# Pinscape_Pico-KL25Z_Adapter.net
KiCad netlist of a schematic drawn in EAGLE
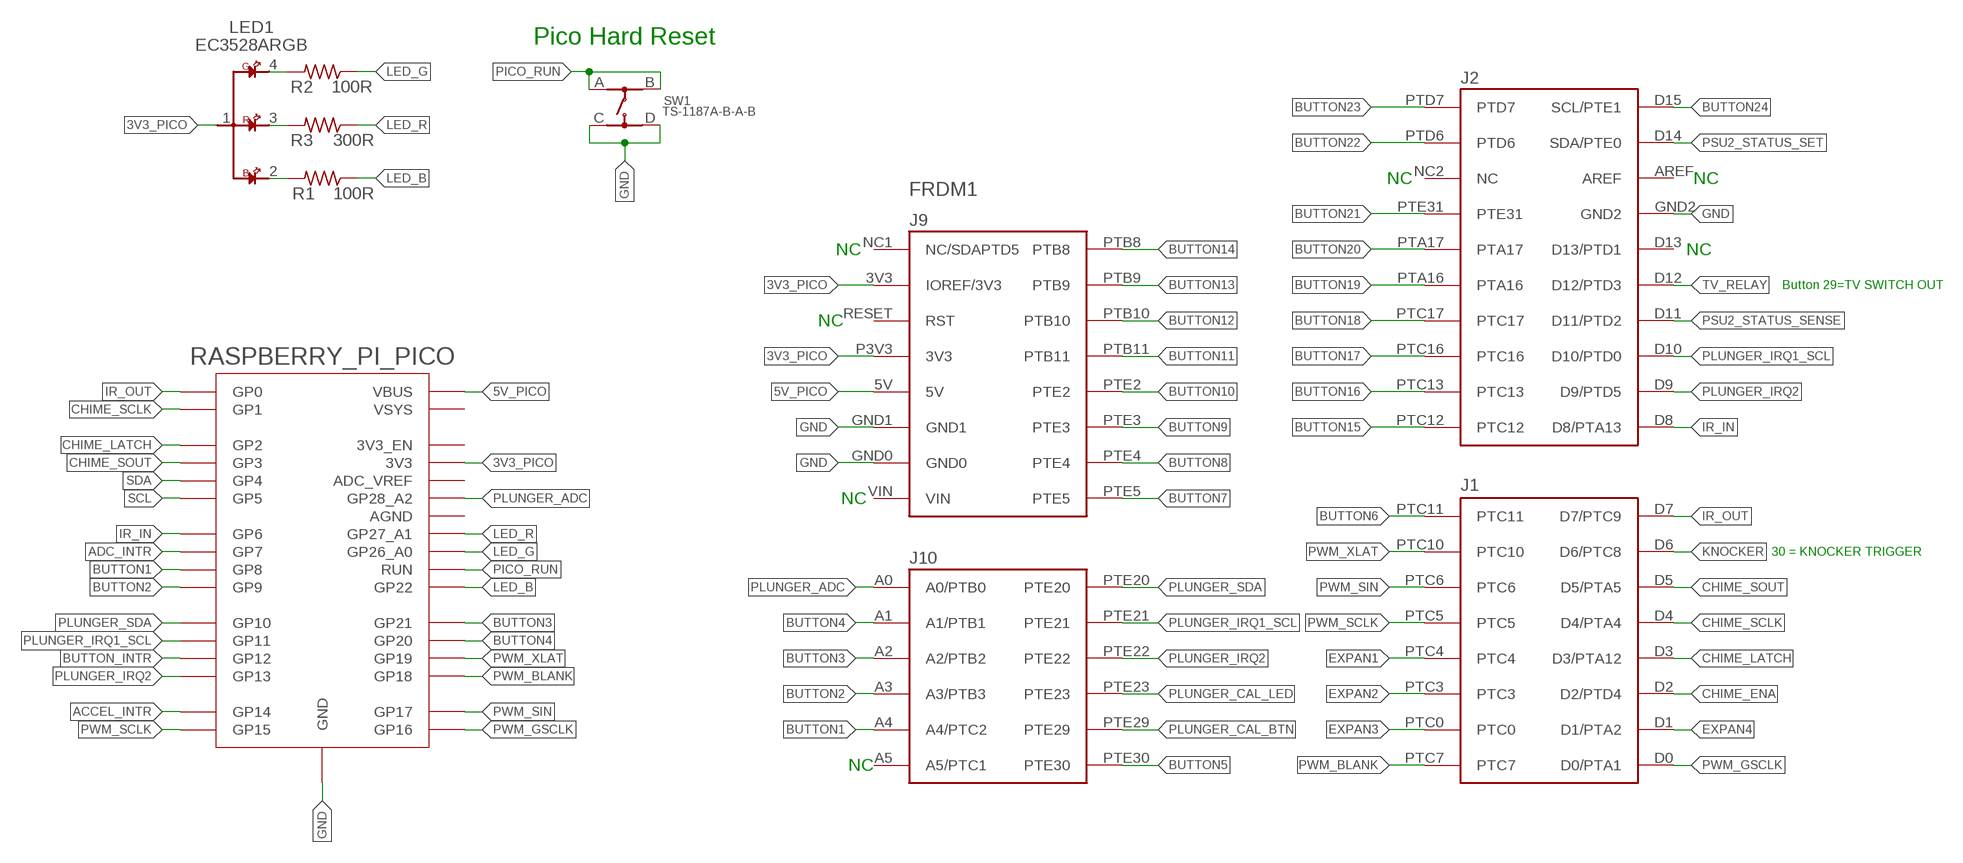
[diagram p0: schematic, sheet 1]
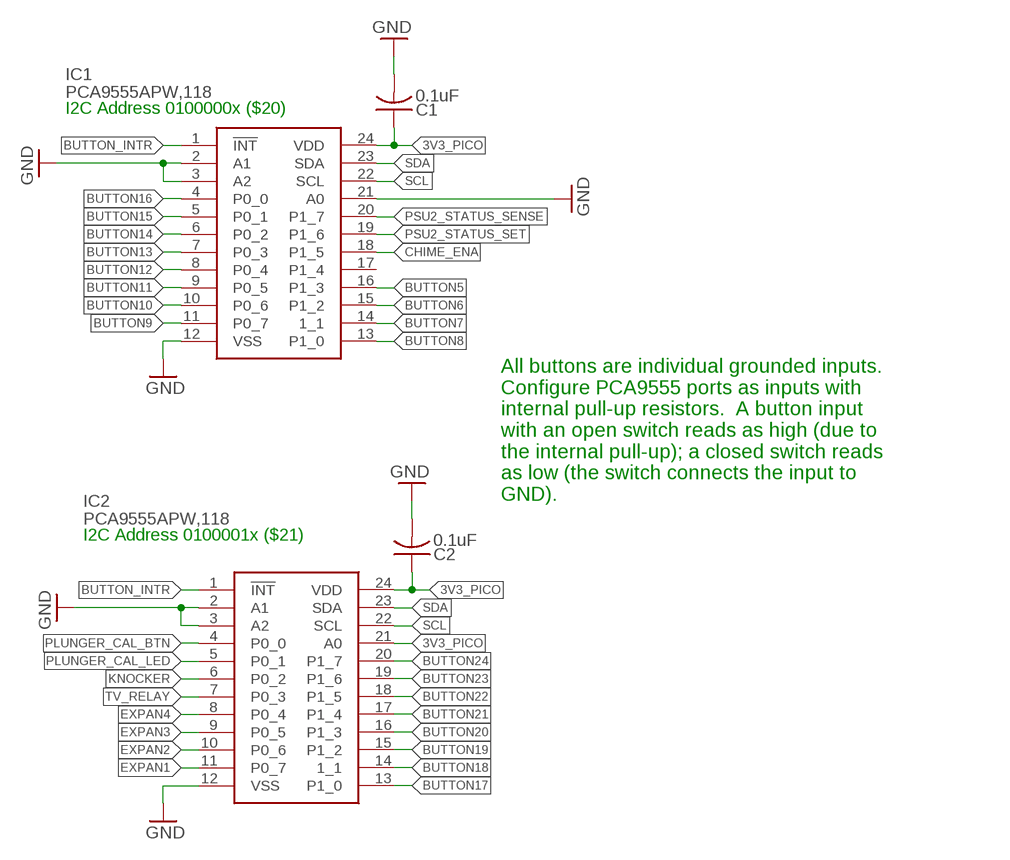
[diagram p1: schematic, sheet 2]
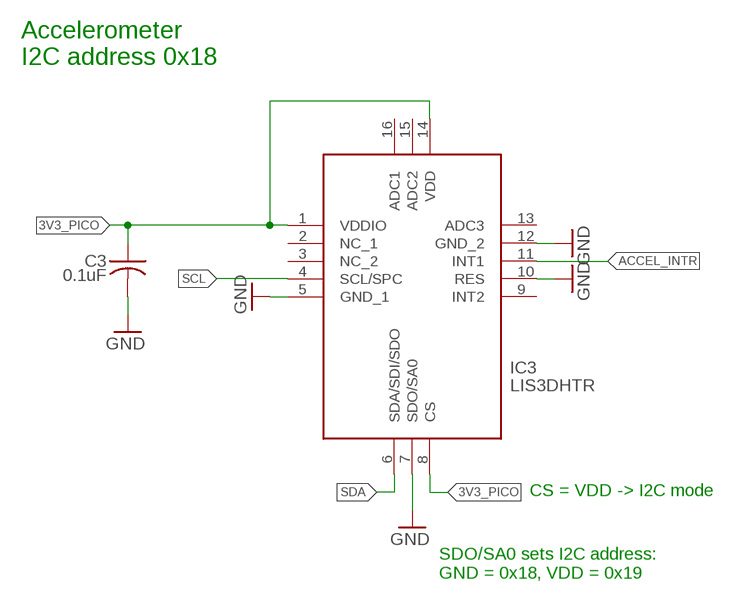
[diagram p2: schematic, sheet 3]
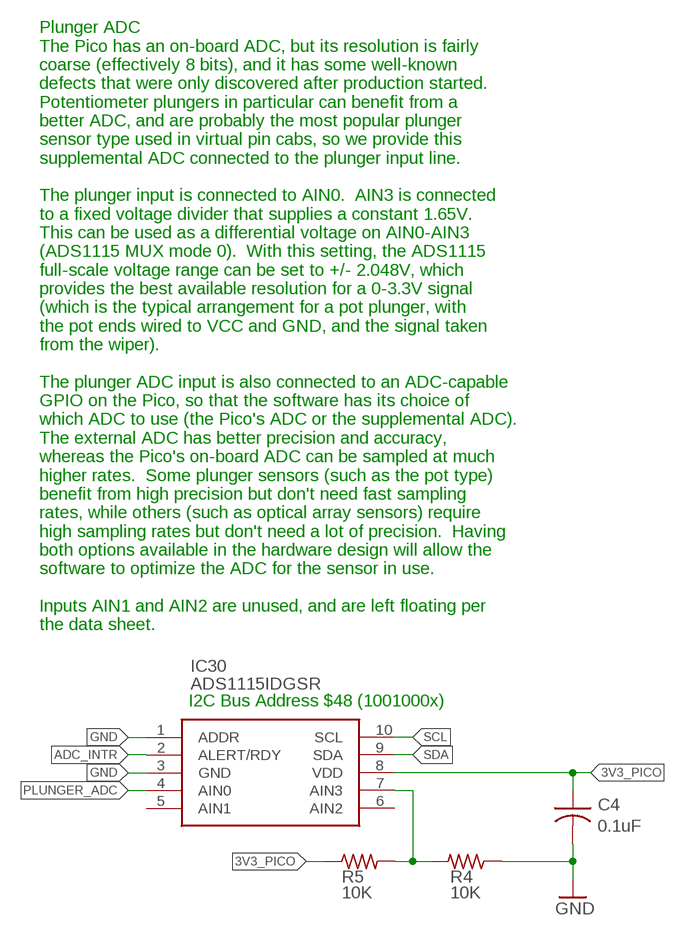
[diagram p3: schematic, sheet 4]

(export (version "E")
  (design (tool "Eeschema 10.0.6"))
  (components
    (comp (ref "FRDM1")
      (value "KL25Z")
      (footprint "eagle-import:FRDM_KL25Z_NORMAL")
      (libsource (lib "eagle-import") (part "FRDM-KL25ZNORMAL"))
    )
    (comp (ref "LED1")
      (value "EC3528ARGB")
      (footprint "eagle-import:EC3528ARGB")
      (libsource (lib "eagle-import") (part "EC3528ARGB"))
    )
    (comp (ref "R1")
      (value "100R")
      (footprint "eagle-import:R1206")
      (libsource (lib "eagle-import") (part "R-US_R1206"))
    )
    (comp (ref "R2")
      (value "100R")
      (footprint "eagle-import:R1206")
      (libsource (lib "eagle-import") (part "R-US_R1206"))
    )
    (comp (ref "R3")
      (value "300R")
      (footprint "eagle-import:R1206")
      (libsource (lib "eagle-import") (part "R-US_R1206"))
    )
    (comp (ref "RASPBERRY_PI_PICO")
      (value "RPI_PICO_NO_DEBUG")
      (footprint "eagle-import:RPI_PICO_TH_NO_DEBUG")
      (libsource (lib "eagle-import") (part "RPI_PICO_NO_DEBUG"))
    )
    (comp (ref "SW1")
      (value "TS-1187A-B-A-B")
      (footprint "eagle-import:TS-1187A-B-A-B")
      (libsource (lib "eagle-import") (part "TS-1187A-B-A-B"))
    )
    (comp (ref "C1")
      (value "0.1uF")
      (footprint "eagle-import:C1206")
      (libsource (lib "eagle-import") (part "C-USC1206"))
    )
    (comp (ref "C2")
      (value "0.1uF")
      (footprint "eagle-import:C1206")
      (libsource (lib "eagle-import") (part "C-USC1206"))
    )
    (comp (ref "IC1")
      (value "PCA9555APW,118")
      (footprint "eagle-import:SOP65P640X110-24N")
      (fields (field (name "MOUSER_PART_NUMBER") "771-PCA9555APW118"))
      (libsource (lib "eagle-import") (part "PCA9555APW,118"))
    )
    (comp (ref "IC2")
      (value "PCA9555APW,118")
      (footprint "eagle-import:SOP65P640X110-24N")
      (fields (field (name "MOUSER_PART_NUMBER") "771-PCA9555APW118"))
      (libsource (lib "eagle-import") (part "PCA9555APW,118"))
    )
    (comp (ref "C4")
      (value "0.1uF")
      (footprint "eagle-import:C1206")
      (libsource (lib "eagle-import") (part "C-USC1206"))
    )
    (comp (ref "IC30")
      (value "ADS1115IDGSR")
      (footprint "eagle-import:SOP50P490X110-10N")
      (fields (field (name "MOUSER_PART_NUMBER") "595-ADS1115IDGSR"))
      (libsource (lib "eagle-import") (part "ADS1115IDGSR"))
    )
    (comp (ref "R4")
      (value "10K")
      (footprint "eagle-import:R1206")
      (libsource (lib "eagle-import") (part "R-US_R1206"))
    )
    (comp (ref "R5")
      (value "10K")
      (footprint "eagle-import:R1206")
      (libsource (lib "eagle-import") (part "R-US_R1206"))
    )
    (comp (ref "C3")
      (value "0.1uF")
      (footprint "eagle-import:C1206")
      (libsource (lib "eagle-import") (part "C-USC1206"))
    )
    (comp (ref "IC3")
      (value "LIS3DHTR")
      (footprint "eagle-import:LIS3DHTR")
      (fields (field (name "MOUSER_PART_NUMBER") "511-LIS3DHTR"))
      (libsource (lib "eagle-import") (part "LIS3DHTR"))
    )
  )
  (nets
    (net (code "1") (name "3V3_PICO") (class "Default")
      (node (ref "C1") (pin "1") (pinfunction "1_1") (pintype "passive"))
      (node (ref "C2") (pin "1") (pinfunction "1_1") (pintype "passive"))
      (node (ref "C3") (pin "1") (pinfunction "1_1") (pintype "passive"))
      (node (ref "C4") (pin "1") (pinfunction "1_1") (pintype "passive"))
      (node (ref "FRDM1") (pin "3V3") (pinfunction "IOREF/3V3_3V3") (pintype "bidirectional"))
      (node (ref "FRDM1") (pin "P3V3") (pinfunction "3V3_P3V3") (pintype "bidirectional"))
      (node (ref "IC1") (pin "24") (pinfunction "VDD_24") (pintype "bidirectional"))
      (node (ref "IC2") (pin "21") (pinfunction "A0_21") (pintype "bidirectional"))
      (node (ref "IC2") (pin "24") (pinfunction "VDD_24") (pintype "bidirectional"))
      (node (ref "IC3") (pin "1") (pinfunction "VDDIO_1") (pintype "power_in"))
      (node (ref "IC3") (pin "14") (pinfunction "VDD_14") (pintype "power_in"))
      (node (ref "IC3") (pin "8") (pinfunction "CS_8") (pintype "input"))
      (node (ref "IC30") (pin "8") (pinfunction "VDD_8") (pintype "bidirectional"))
      (node (ref "LED1") (pin "1") (pinfunction "1_1") (pintype "bidirectional"))
      (node (ref "R5") (pin "1") (pinfunction "1_1") (pintype "passive"))
      (node (ref "RASPBERRY_PI_PICO") (pin "3V3") (pinfunction "3V3_3V3") (pintype "bidirectional"))
    )
    (net (code "2") (name "5V_PICO") (class "Default")
      (node (ref "FRDM1") (pin "5V") (pinfunction "5V_5V") (pintype "bidirectional"))
      (node (ref "RASPBERRY_PI_PICO") (pin "VBUS") (pinfunction "VBUS_VBUS") (pintype "bidirectional"))
    )
    (net (code "3") (name "ACCEL_INTR") (class "Default")
      (node (ref "IC3") (pin "11") (pinfunction "INT1_11") (pintype "input"))
      (node (ref "RASPBERRY_PI_PICO") (pin "GP14") (pinfunction "GP14_GP14") (pintype "bidirectional"))
    )
    (net (code "4") (name "ADC_INTR") (class "Default")
      (node (ref "IC30") (pin "2") (pinfunction "ALERT/RDY_2") (pintype "bidirectional"))
      (node (ref "RASPBERRY_PI_PICO") (pin "GP7") (pinfunction "GP7_GP7") (pintype "bidirectional"))
    )
    (net (code "5") (name "BUTTON1") (class "Default")
      (node (ref "FRDM1") (pin "A4") (pinfunction "A4/PTC2_A4") (pintype "bidirectional"))
      (node (ref "RASPBERRY_PI_PICO") (pin "GP8") (pinfunction "GP8_GP8") (pintype "bidirectional"))
    )
    (net (code "6") (name "BUTTON2") (class "Default")
      (node (ref "FRDM1") (pin "A3") (pinfunction "A3/PTB3_A3") (pintype "bidirectional"))
      (node (ref "RASPBERRY_PI_PICO") (pin "GP9") (pinfunction "GP9_GP9") (pintype "bidirectional"))
    )
    (net (code "7") (name "BUTTON3") (class "Default")
      (node (ref "FRDM1") (pin "A2") (pinfunction "A2/PTB2_A2") (pintype "bidirectional"))
      (node (ref "RASPBERRY_PI_PICO") (pin "GP21") (pinfunction "GP21_GP21") (pintype "bidirectional"))
    )
    (net (code "8") (name "BUTTON4") (class "Default")
      (node (ref "FRDM1") (pin "A1") (pinfunction "A1/PTB1_A1") (pintype "bidirectional"))
      (node (ref "RASPBERRY_PI_PICO") (pin "GP20") (pinfunction "GP20_GP20") (pintype "bidirectional"))
    )
    (net (code "9") (name "BUTTON5") (class "Default")
      (node (ref "FRDM1") (pin "PTE30") (pinfunction "PTE30_PTE30") (pintype "bidirectional"))
      (node (ref "IC1") (pin "16") (pinfunction "P1_3_16") (pintype "bidirectional"))
    )
    (net (code "10") (name "BUTTON6") (class "Default")
      (node (ref "FRDM1") (pin "PTC11") (pinfunction "PTC11_PTC11") (pintype "bidirectional"))
      (node (ref "IC1") (pin "15") (pinfunction "P1_2_15") (pintype "bidirectional"))
    )
    (net (code "11") (name "BUTTON7") (class "Default")
      (node (ref "FRDM1") (pin "PTE5") (pinfunction "PTE5_PTE5") (pintype "bidirectional"))
      (node (ref "IC1") (pin "14") (pinfunction "1_1_14") (pintype "bidirectional"))
    )
    (net (code "12") (name "BUTTON8") (class "Default")
      (node (ref "FRDM1") (pin "PTE4") (pinfunction "PTE4_PTE4") (pintype "bidirectional"))
      (node (ref "IC1") (pin "13") (pinfunction "P1_0_13") (pintype "bidirectional"))
    )
    (net (code "13") (name "BUTTON9") (class "Default")
      (node (ref "FRDM1") (pin "PTE3") (pinfunction "PTE3_PTE3") (pintype "bidirectional"))
      (node (ref "IC1") (pin "11") (pinfunction "P0_7_11") (pintype "bidirectional"))
    )
    (net (code "14") (name "BUTTON10") (class "Default")
      (node (ref "FRDM1") (pin "PTE2") (pinfunction "PTE2_PTE2") (pintype "bidirectional"))
      (node (ref "IC1") (pin "10") (pinfunction "P0_6_10") (pintype "bidirectional"))
    )
    (net (code "15") (name "BUTTON11") (class "Default")
      (node (ref "FRDM1") (pin "PTB11") (pinfunction "PTB11_PTB11") (pintype "bidirectional"))
      (node (ref "IC1") (pin "9") (pinfunction "P0_5_9") (pintype "bidirectional"))
    )
    (net (code "16") (name "BUTTON12") (class "Default")
      (node (ref "FRDM1") (pin "PTB10") (pinfunction "PTB10_PTB10") (pintype "bidirectional"))
      (node (ref "IC1") (pin "8") (pinfunction "P0_4_8") (pintype "bidirectional"))
    )
    (net (code "17") (name "BUTTON13") (class "Default")
      (node (ref "FRDM1") (pin "PTB9") (pinfunction "PTB9_PTB9") (pintype "bidirectional"))
      (node (ref "IC1") (pin "7") (pinfunction "P0_3_7") (pintype "bidirectional"))
    )
    (net (code "18") (name "BUTTON14") (class "Default")
      (node (ref "FRDM1") (pin "PTB8") (pinfunction "PTB8_PTB8") (pintype "bidirectional"))
      (node (ref "IC1") (pin "6") (pinfunction "P0_2_6") (pintype "bidirectional"))
    )
    (net (code "19") (name "BUTTON15") (class "Default")
      (node (ref "FRDM1") (pin "PTC12") (pinfunction "PTC12_PTC12") (pintype "bidirectional"))
      (node (ref "IC1") (pin "5") (pinfunction "P0_1_5") (pintype "bidirectional"))
    )
    (net (code "20") (name "BUTTON16") (class "Default")
      (node (ref "FRDM1") (pin "PTC13") (pinfunction "PTC13_PTC13") (pintype "bidirectional"))
      (node (ref "IC1") (pin "4") (pinfunction "P0_0_4") (pintype "bidirectional"))
    )
    (net (code "21") (name "BUTTON17") (class "Default")
      (node (ref "FRDM1") (pin "PTC16") (pinfunction "PTC16_PTC16") (pintype "bidirectional"))
      (node (ref "IC2") (pin "13") (pinfunction "P1_0_13") (pintype "bidirectional"))
    )
    (net (code "22") (name "BUTTON18") (class "Default")
      (node (ref "FRDM1") (pin "PTC17") (pinfunction "PTC17_PTC17") (pintype "bidirectional"))
      (node (ref "IC2") (pin "14") (pinfunction "1_1_14") (pintype "bidirectional"))
    )
    (net (code "23") (name "BUTTON19") (class "Default")
      (node (ref "FRDM1") (pin "PTA16") (pinfunction "PTA16_PTA16") (pintype "bidirectional"))
      (node (ref "IC2") (pin "15") (pinfunction "P1_2_15") (pintype "bidirectional"))
    )
    (net (code "24") (name "BUTTON20") (class "Default")
      (node (ref "FRDM1") (pin "PTA17") (pinfunction "PTA17_PTA17") (pintype "bidirectional"))
      (node (ref "IC2") (pin "16") (pinfunction "P1_3_16") (pintype "bidirectional"))
    )
    (net (code "25") (name "BUTTON21") (class "Default")
      (node (ref "FRDM1") (pin "PTE31") (pinfunction "PTE31_PTE31") (pintype "bidirectional"))
      (node (ref "IC2") (pin "17") (pinfunction "P1_4_17") (pintype "bidirectional"))
    )
    (net (code "26") (name "BUTTON22") (class "Default")
      (node (ref "FRDM1") (pin "PTD6") (pinfunction "PTD6_PTD6") (pintype "bidirectional"))
      (node (ref "IC2") (pin "18") (pinfunction "P1_5_18") (pintype "bidirectional"))
    )
    (net (code "27") (name "BUTTON23") (class "Default")
      (node (ref "FRDM1") (pin "PTD7") (pinfunction "PTD7_PTD7") (pintype "bidirectional"))
      (node (ref "IC2") (pin "19") (pinfunction "P1_6_19") (pintype "bidirectional"))
    )
    (net (code "28") (name "BUTTON24") (class "Default")
      (node (ref "FRDM1") (pin "D15") (pinfunction "SCL/PTE1_D15") (pintype "bidirectional"))
      (node (ref "IC2") (pin "20") (pinfunction "P1_7_20") (pintype "bidirectional"))
    )
    (net (code "29") (name "BUTTON_INTR") (class "Default")
      (node (ref "IC1") (pin "1") (pinfunction "~{INT}_1") (pintype "bidirectional"))
      (node (ref "IC2") (pin "1") (pinfunction "~{INT}_1") (pintype "bidirectional"))
      (node (ref "RASPBERRY_PI_PICO") (pin "GP12") (pinfunction "GP12_GP12") (pintype "bidirectional"))
    )
    (net (code "30") (name "CHIME_ENA") (class "Default")
      (node (ref "FRDM1") (pin "D2") (pinfunction "D2/PTD4_D2") (pintype "bidirectional"))
      (node (ref "IC1") (pin "18") (pinfunction "P1_5_18") (pintype "bidirectional"))
    )
    (net (code "31") (name "CHIME_LATCH") (class "Default")
      (node (ref "FRDM1") (pin "D3") (pinfunction "D3/PTA12_D3") (pintype "bidirectional"))
      (node (ref "RASPBERRY_PI_PICO") (pin "GP2") (pinfunction "GP2_GP2") (pintype "bidirectional"))
    )
    (net (code "32") (name "CHIME_SCLK") (class "Default")
      (node (ref "FRDM1") (pin "D4") (pinfunction "D4/PTA4_D4") (pintype "bidirectional"))
      (node (ref "RASPBERRY_PI_PICO") (pin "GP1") (pinfunction "GP1_GP1") (pintype "bidirectional"))
    )
    (net (code "33") (name "CHIME_SOUT") (class "Default")
      (node (ref "FRDM1") (pin "D5") (pinfunction "D5/PTA5_D5") (pintype "bidirectional"))
      (node (ref "RASPBERRY_PI_PICO") (pin "GP3") (pinfunction "GP3_GP3") (pintype "bidirectional"))
    )
    (net (code "34") (name "EXPAN1") (class "Default")
      (node (ref "FRDM1") (pin "PTC4") (pinfunction "PTC4_PTC4") (pintype "bidirectional"))
      (node (ref "IC2") (pin "11") (pinfunction "P0_7_11") (pintype "bidirectional"))
    )
    (net (code "35") (name "EXPAN2") (class "Default")
      (node (ref "FRDM1") (pin "PTC3") (pinfunction "PTC3_PTC3") (pintype "bidirectional"))
      (node (ref "IC2") (pin "10") (pinfunction "P0_6_10") (pintype "bidirectional"))
    )
    (net (code "36") (name "EXPAN3") (class "Default")
      (node (ref "FRDM1") (pin "PTC0") (pinfunction "PTC0_PTC0") (pintype "bidirectional"))
      (node (ref "IC2") (pin "9") (pinfunction "P0_5_9") (pintype "bidirectional"))
    )
    (net (code "37") (name "EXPAN4") (class "Default")
      (node (ref "FRDM1") (pin "D1") (pinfunction "D1/PTA2_D1") (pintype "bidirectional"))
      (node (ref "IC2") (pin "8") (pinfunction "P0_4_8") (pintype "bidirectional"))
    )
    (net (code "38") (name "GND") (class "Default")
      (node (ref "C1") (pin "2") (pinfunction "2_2") (pintype "passive"))
      (node (ref "C2") (pin "2") (pinfunction "2_2") (pintype "passive"))
      (node (ref "C3") (pin "2") (pinfunction "2_2") (pintype "passive"))
      (node (ref "C4") (pin "2") (pinfunction "2_2") (pintype "passive"))
      (node (ref "FRDM1") (pin "GND0") (pinfunction "GND0_GND0") (pintype "bidirectional"))
      (node (ref "FRDM1") (pin "GND1") (pinfunction "GND1_GND1") (pintype "bidirectional"))
      (node (ref "FRDM1") (pin "GND2") (pinfunction "GND2_GND2") (pintype "bidirectional"))
      (node (ref "IC1") (pin "12") (pinfunction "VSS_12") (pintype "bidirectional"))
      (node (ref "IC1") (pin "2") (pinfunction "A1_2") (pintype "bidirectional"))
      (node (ref "IC1") (pin "21") (pinfunction "A0_21") (pintype "bidirectional"))
      (node (ref "IC1") (pin "3") (pinfunction "A2_3") (pintype "bidirectional"))
      (node (ref "IC2") (pin "12") (pinfunction "VSS_12") (pintype "bidirectional"))
      (node (ref "IC2") (pin "2") (pinfunction "A1_2") (pintype "bidirectional"))
      (node (ref "IC2") (pin "3") (pinfunction "A2_3") (pintype "bidirectional"))
      (node (ref "IC3") (pin "10") (pinfunction "RES_10") (pintype "bidirectional"))
      (node (ref "IC3") (pin "12") (pinfunction "GND_2_12") (pintype "power_in"))
      (node (ref "IC3") (pin "5") (pinfunction "GND_1_5") (pintype "power_in"))
      (node (ref "IC3") (pin "7") (pinfunction "SDO/SA0_7") (pintype "bidirectional"))
      (node (ref "IC30") (pin "1") (pinfunction "ADDR_1") (pintype "bidirectional"))
      (node (ref "IC30") (pin "3") (pinfunction "GND_3") (pintype "bidirectional"))
      (node (ref "R4") (pin "1") (pinfunction "1_1") (pintype "passive"))
      (node (ref "RASPBERRY_PI_PICO") (pin "GND@1") (pinfunction "GND_GND@1") (pintype "bidirectional"))
      (node (ref "RASPBERRY_PI_PICO") (pin "GND@2") (pinfunction "GND_GND@2") (pintype "bidirectional"))
      (node (ref "RASPBERRY_PI_PICO") (pin "GND@3") (pinfunction "GND_GND@3") (pintype "bidirectional"))
      (node (ref "RASPBERRY_PI_PICO") (pin "GND@4") (pinfunction "GND_GND@4") (pintype "bidirectional"))
      (node (ref "RASPBERRY_PI_PICO") (pin "GND@6") (pinfunction "GND_GND@6") (pintype "bidirectional"))
      (node (ref "RASPBERRY_PI_PICO") (pin "GND@7") (pinfunction "GND_GND@7") (pintype "bidirectional"))
      (node (ref "RASPBERRY_PI_PICO") (pin "GND@8") (pinfunction "GND_GND@8") (pintype "bidirectional"))
      (node (ref "SW1") (pin "C") (pinfunction "C_C") (pintype "bidirectional"))
      (node (ref "SW1") (pin "D") (pinfunction "D_D") (pintype "bidirectional"))
    )
    (net (code "39") (name "IR_IN") (class "Default")
      (node (ref "FRDM1") (pin "D8") (pinfunction "D8/PTA13_D8") (pintype "bidirectional"))
      (node (ref "RASPBERRY_PI_PICO") (pin "GP6") (pinfunction "GP6_GP6") (pintype "bidirectional"))
    )
    (net (code "40") (name "IR_OUT") (class "Default")
      (node (ref "FRDM1") (pin "D7") (pinfunction "D7/PTC9_D7") (pintype "bidirectional"))
      (node (ref "RASPBERRY_PI_PICO") (pin "GP0") (pinfunction "GP0_GP0") (pintype "bidirectional"))
    )
    (net (code "41") (name "KNOCKER") (class "Default")
      (node (ref "FRDM1") (pin "D6") (pinfunction "D6/PTC8_D6") (pintype "bidirectional"))
      (node (ref "IC2") (pin "6") (pinfunction "P0_2_6") (pintype "bidirectional"))
    )
    (net (code "42") (name "LED_B") (class "Default")
      (node (ref "R1") (pin "1") (pinfunction "1_1") (pintype "passive"))
      (node (ref "RASPBERRY_PI_PICO") (pin "GP22") (pinfunction "GP22_GP22") (pintype "bidirectional"))
    )
    (net (code "43") (name "LED_G") (class "Default")
      (node (ref "R2") (pin "1") (pinfunction "1_1") (pintype "passive"))
      (node (ref "RASPBERRY_PI_PICO") (pin "GP26_A0") (pinfunction "GP26_A0_GP26_A0") (pintype "bidirectional"))
    )
    (net (code "44") (name "LED_R") (class "Default")
      (node (ref "R3") (pin "1") (pinfunction "1_1") (pintype "passive"))
      (node (ref "RASPBERRY_PI_PICO") (pin "GP27_A1") (pinfunction "GP27_A1_GP27_A1") (pintype "bidirectional"))
    )
    (net (code "45") (name "Net-(IC30-AIN3)") (class "Default")
      (node (ref "IC30") (pin "7") (pinfunction "AIN3_7") (pintype "bidirectional"))
      (node (ref "R4") (pin "2") (pinfunction "2_2") (pintype "passive"))
      (node (ref "R5") (pin "2") (pinfunction "2_2") (pintype "passive"))
    )
    (net (code "46") (name "Net-(LED1-Pad2)") (class "Default")
      (node (ref "LED1") (pin "2") (pinfunction "2_2") (pintype "bidirectional"))
      (node (ref "R1") (pin "2") (pinfunction "2_2") (pintype "passive"))
    )
    (net (code "47") (name "Net-(LED1-Pad3)") (class "Default")
      (node (ref "LED1") (pin "3") (pinfunction "3_3") (pintype "bidirectional"))
      (node (ref "R3") (pin "2") (pinfunction "2_2") (pintype "passive"))
    )
    (net (code "48") (name "Net-(LED1-Pad4)") (class "Default")
      (node (ref "LED1") (pin "4") (pinfunction "4_4") (pintype "bidirectional"))
      (node (ref "R2") (pin "2") (pinfunction "2_2") (pintype "passive"))
    )
    (net (code "49") (name "PICO_RUN") (class "Default")
      (node (ref "RASPBERRY_PI_PICO") (pin "RUN") (pinfunction "RUN_RUN") (pintype "bidirectional"))
      (node (ref "SW1") (pin "A") (pinfunction "A_A") (pintype "bidirectional"))
      (node (ref "SW1") (pin "B") (pinfunction "B_B") (pintype "bidirectional"))
    )
    (net (code "50") (name "PLUNGER_ADC") (class "Default")
      (node (ref "FRDM1") (pin "A0") (pinfunction "A0/PTB0_A0") (pintype "bidirectional"))
      (node (ref "IC30") (pin "4") (pinfunction "AIN0_4") (pintype "bidirectional"))
      (node (ref "RASPBERRY_PI_PICO") (pin "GP28_A2") (pinfunction "GP28_A2_GP28_A2") (pintype "bidirectional"))
    )
    (net (code "51") (name "PLUNGER_CAL_BTN") (class "Default")
      (node (ref "FRDM1") (pin "PTE29") (pinfunction "PTE29_PTE29") (pintype "bidirectional"))
      (node (ref "IC2") (pin "4") (pinfunction "P0_0_4") (pintype "bidirectional"))
    )
    (net (code "52") (name "PLUNGER_CAL_LED") (class "Default")
      (node (ref "FRDM1") (pin "PTE23") (pinfunction "PTE23_PTE23") (pintype "bidirectional"))
      (node (ref "IC2") (pin "5") (pinfunction "P0_1_5") (pintype "bidirectional"))
    )
    (net (code "53") (name "PLUNGER_IRQ1_SCL") (class "Default")
      (node (ref "FRDM1") (pin "D10") (pinfunction "D10/PTD0_D10") (pintype "bidirectional"))
      (node (ref "FRDM1") (pin "PTE21") (pinfunction "PTE21_PTE21") (pintype "bidirectional"))
      (node (ref "RASPBERRY_PI_PICO") (pin "GP11") (pinfunction "GP11_GP11") (pintype "bidirectional"))
    )
    (net (code "54") (name "PLUNGER_IRQ2") (class "Default")
      (node (ref "FRDM1") (pin "D9") (pinfunction "D9/PTD5_D9") (pintype "bidirectional"))
      (node (ref "FRDM1") (pin "PTE22") (pinfunction "PTE22_PTE22") (pintype "bidirectional"))
      (node (ref "RASPBERRY_PI_PICO") (pin "GP13") (pinfunction "GP13_GP13") (pintype "bidirectional"))
    )
    (net (code "55") (name "PLUNGER_SDA") (class "Default")
      (node (ref "FRDM1") (pin "PTE20") (pinfunction "PTE20_PTE20") (pintype "bidirectional"))
      (node (ref "RASPBERRY_PI_PICO") (pin "GP10") (pinfunction "GP10_GP10") (pintype "bidirectional"))
    )
    (net (code "56") (name "PSU2_STATUS_SENSE") (class "Default")
      (node (ref "FRDM1") (pin "D11") (pinfunction "D11/PTD2_D11") (pintype "bidirectional"))
      (node (ref "IC1") (pin "20") (pinfunction "P1_7_20") (pintype "bidirectional"))
    )
    (net (code "57") (name "PSU2_STATUS_SET") (class "Default")
      (node (ref "FRDM1") (pin "D14") (pinfunction "SDA/PTE0_D14") (pintype "bidirectional"))
      (node (ref "IC1") (pin "19") (pinfunction "P1_6_19") (pintype "bidirectional"))
    )
    (net (code "58") (name "PWM_BLANK") (class "Default")
      (node (ref "FRDM1") (pin "PTC7") (pinfunction "PTC7_PTC7") (pintype "bidirectional"))
      (node (ref "RASPBERRY_PI_PICO") (pin "GP18") (pinfunction "GP18_GP18") (pintype "bidirectional"))
    )
    (net (code "59") (name "PWM_GSCLK") (class "Default")
      (node (ref "FRDM1") (pin "D0") (pinfunction "D0/PTA1_D0") (pintype "bidirectional"))
      (node (ref "RASPBERRY_PI_PICO") (pin "GP16") (pinfunction "GP16_GP16") (pintype "bidirectional"))
    )
    (net (code "60") (name "PWM_SCLK") (class "Default")
      (node (ref "FRDM1") (pin "PTC5") (pinfunction "PTC5_PTC5") (pintype "bidirectional"))
      (node (ref "RASPBERRY_PI_PICO") (pin "GP15") (pinfunction "GP15_GP15") (pintype "bidirectional"))
    )
    (net (code "61") (name "PWM_SIN") (class "Default")
      (node (ref "FRDM1") (pin "PTC6") (pinfunction "PTC6_PTC6") (pintype "bidirectional"))
      (node (ref "RASPBERRY_PI_PICO") (pin "GP17") (pinfunction "GP17_GP17") (pintype "bidirectional"))
    )
    (net (code "62") (name "PWM_XLAT") (class "Default")
      (node (ref "FRDM1") (pin "PTC10") (pinfunction "PTC10_PTC10") (pintype "bidirectional"))
      (node (ref "RASPBERRY_PI_PICO") (pin "GP19") (pinfunction "GP19_GP19") (pintype "bidirectional"))
    )
    (net (code "63") (name "SCL") (class "Default")
      (node (ref "IC1") (pin "22") (pinfunction "SCL_22") (pintype "bidirectional"))
      (node (ref "IC2") (pin "22") (pinfunction "SCL_22") (pintype "bidirectional"))
      (node (ref "IC3") (pin "4") (pinfunction "SCL/SPC_4") (pintype "bidirectional"))
      (node (ref "IC30") (pin "10") (pinfunction "SCL_10") (pintype "bidirectional"))
      (node (ref "RASPBERRY_PI_PICO") (pin "GP5") (pinfunction "GP5_GP5") (pintype "bidirectional"))
    )
    (net (code "64") (name "SDA") (class "Default")
      (node (ref "IC1") (pin "23") (pinfunction "SDA_23") (pintype "bidirectional"))
      (node (ref "IC2") (pin "23") (pinfunction "SDA_23") (pintype "bidirectional"))
      (node (ref "IC3") (pin "6") (pinfunction "SDA/SDI/SDO_6") (pintype "bidirectional"))
      (node (ref "IC30") (pin "9") (pinfunction "SDA_9") (pintype "bidirectional"))
      (node (ref "RASPBERRY_PI_PICO") (pin "GP4") (pinfunction "GP4_GP4") (pintype "bidirectional"))
    )
    (net (code "65") (name "TV_RELAY") (class "Default")
      (node (ref "FRDM1") (pin "D12") (pinfunction "D12/PTD3_D12") (pintype "bidirectional"))
      (node (ref "IC2") (pin "7") (pinfunction "P0_3_7") (pintype "bidirectional"))
    )
    (net (code "66") (name "unconnected-(FRDM1-A5{slash}PTC1-PadA5)") (class "Default")
      (node (ref "FRDM1") (pin "A5") (pinfunction "A5/PTC1_A5") (pintype "bidirectional"))
    )
    (net (code "67") (name "unconnected-(FRDM1-D13{slash}PTD1-PadD13)") (class "Default")
      (node (ref "FRDM1") (pin "D13") (pinfunction "D13/PTD1_D13") (pintype "bidirectional"))
    )
    (net (code "68") (name "unconnected-(FRDM1-NC-PadNC2)") (class "Default")
      (node (ref "FRDM1") (pin "NC2") (pinfunction "NC_NC2") (pintype "bidirectional"))
    )
    (net (code "69") (name "unconnected-(FRDM1-NC{slash}SDAPTD5-PadNC1)") (class "Default")
      (node (ref "FRDM1") (pin "NC1") (pinfunction "NC/SDAPTD5_NC1") (pintype "bidirectional"))
    )
    (net (code "70") (name "unconnected-(FRDM1-PadAREF)") (class "Default")
      (node (ref "FRDM1") (pin "AREF") (pinfunction "AREF_AREF") (pintype "bidirectional"))
    )
    (net (code "71") (name "unconnected-(FRDM1-PadVIN)") (class "Default")
      (node (ref "FRDM1") (pin "VIN") (pinfunction "VIN_VIN") (pintype "bidirectional"))
    )
    (net (code "72") (name "unconnected-(FRDM1-RST-PadRESET)") (class "Default")
      (node (ref "FRDM1") (pin "RESET") (pinfunction "RST_RESET") (pintype "bidirectional"))
    )
    (net (code "73") (name "unconnected-(IC1-P1_4-Pad17)") (class "Default")
      (node (ref "IC1") (pin "17") (pinfunction "P1_4_17") (pintype "bidirectional"))
    )
    (net (code "74") (name "unconnected-(IC3-ADC1-Pad16)") (class "Default")
      (node (ref "IC3") (pin "16") (pinfunction "ADC1_16") (pintype "bidirectional"))
    )
    (net (code "75") (name "unconnected-(IC3-ADC2-Pad15)") (class "Default")
      (node (ref "IC3") (pin "15") (pinfunction "ADC2_15") (pintype "bidirectional"))
    )
    (net (code "76") (name "unconnected-(IC3-ADC3-Pad13)") (class "Default")
      (node (ref "IC3") (pin "13") (pinfunction "ADC3_13") (pintype "bidirectional"))
    )
    (net (code "77") (name "unconnected-(IC3-INT2-Pad9)") (class "Default")
      (node (ref "IC3") (pin "9") (pinfunction "INT2_9") (pintype "input"))
    )
    (net (code "78") (name "unconnected-(IC3-NC_1-Pad2)") (class "Default")
      (node (ref "IC3") (pin "2") (pinfunction "NC_1_2") (pintype "bidirectional"))
    )
    (net (code "79") (name "unconnected-(IC3-NC_2-Pad3)") (class "Default")
      (node (ref "IC3") (pin "3") (pinfunction "NC_2_3") (pintype "bidirectional"))
    )
    (net (code "80") (name "unconnected-(IC30-AIN1-Pad5)") (class "Default")
      (node (ref "IC30") (pin "5") (pinfunction "AIN1_5") (pintype "bidirectional"))
    )
    (net (code "81") (name "unconnected-(IC30-AIN2-Pad6)") (class "Default")
      (node (ref "IC30") (pin "6") (pinfunction "AIN2_6") (pintype "bidirectional"))
    )
    (net (code "82") (name "unconnected-(RASPBERRY_PI_PICO-Pad3V3_EN)") (class "Default")
      (node (ref "RASPBERRY_PI_PICO") (pin "3V3_EN") (pinfunction "3V3_EN_3V3_EN") (pintype "bidirectional"))
    )
    (net (code "83") (name "unconnected-(RASPBERRY_PI_PICO-PadADC_VREF)") (class "Default")
      (node (ref "RASPBERRY_PI_PICO") (pin "ADC_VREF") (pinfunction "ADC_VREF_ADC_VREF") (pintype "bidirectional"))
    )
    (net (code "84") (name "unconnected-(RASPBERRY_PI_PICO-PadAGND)") (class "Default")
      (node (ref "RASPBERRY_PI_PICO") (pin "AGND") (pinfunction "AGND_AGND") (pintype "bidirectional"))
    )
    (net (code "85") (name "unconnected-(RASPBERRY_PI_PICO-PadVSYS)") (class "Default")
      (node (ref "RASPBERRY_PI_PICO") (pin "VSYS") (pinfunction "VSYS_VSYS") (pintype "bidirectional"))
    )
  )
)
